# SCH_Control_unit.net
KiCad netlist of a schematic drawn in EasyEDA
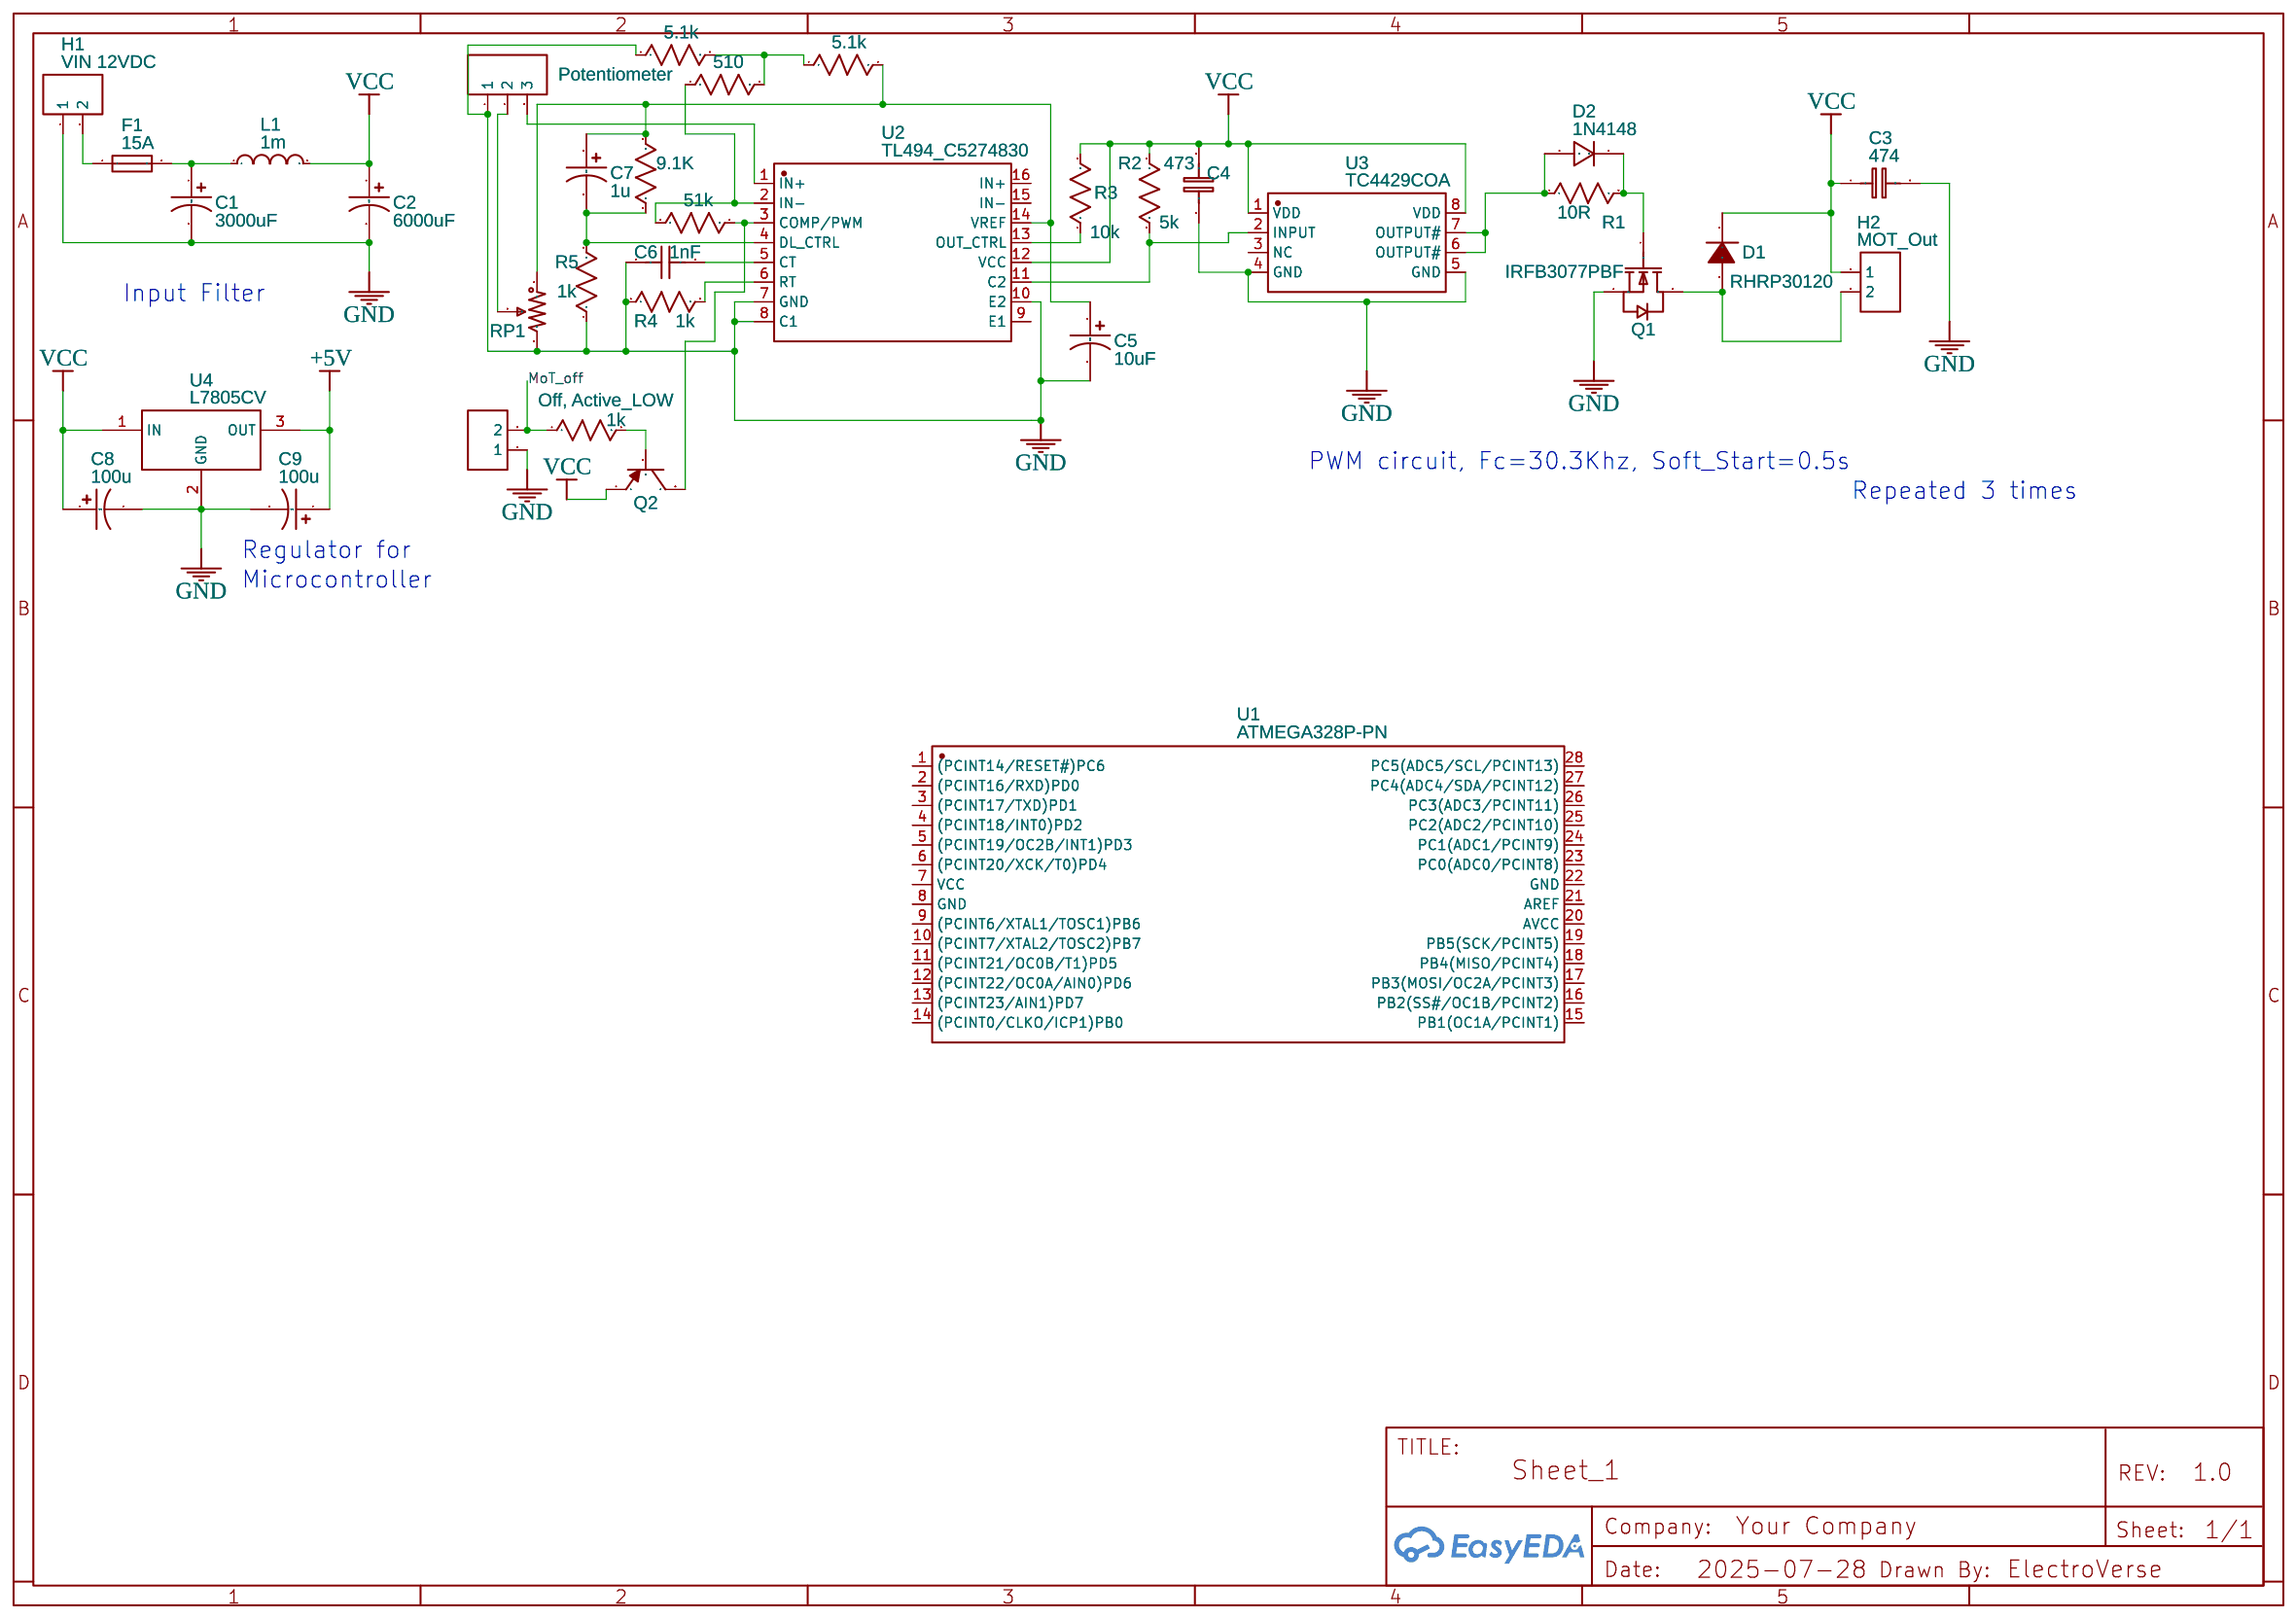
[diagram p0: schematic sheet]

(export (version "E")
  (design (tool "Eeschema 10.0.6"))
  (components
    (comp (ref "C1") (value "3000uF") (libsource (lib "") (part "C_Tan_SMD_A_US")))
    (comp (ref "C2") (value "6000uF") (libsource (lib "") (part "C_Tan_SMD_A_US")))
    (comp (ref "C3") (value "474") (libsource (lib "") (part "C_0603_EU")))
    (comp (ref "C4") (value "473") (libsource (lib "") (part "C_0603_EU_1")))
    (comp (ref "C5") (value "10uF") (libsource (lib "") (part "C_Tan_SMD_A_US_1")))
    (comp (ref "C6") (value "1nF") (libsource (lib "") (part "C_0603_US")))
    (comp (ref "C7") (value "1u") (libsource (lib "") (part "C_Tan_SMD_A_US_1")))
    (comp (ref "C8") (value "100u") (libsource (lib "") (part "C_Tan_SMD_A_US_2")))
    (comp (ref "C9") (value "100u") (libsource (lib "") (part "C_Tan_SMD_A_US_3")))
    (comp (ref "D1")
      (value "RHRP30120")
      (fields (field (name "Manufacturer") "onsemi(安森美)"))
      (libsource (lib "") (part "RHRP30120"))
    )
    (comp (ref "D2")
      (value "1N4148")
      (fields (field (name "Manufacturer") "FMS(美丽微)"))
      (libsource (lib "") (part "1N4148-C163750"))
    )
    (comp (ref "F1")
      (value "15A")
      (fields
        (field (name "Manufacturer Part") "37000500000")
        (field (name "Manufacturer") "Littelfuse(美国力特)")
      )
      (libsource (lib "") (part "37000500000"))
    )
    (comp (ref "H1") (value "VIN 12VDC") (libsource (lib "") (part "HDR-F-2.54_1x2_2")))
    (comp (ref "H2") (value "MOT_Out") (libsource (lib "") (part "HDR-F-2.54_1x2_1")))
    (comp (ref "H3") (value "Potentiometer") (libsource (lib "") (part "HDR-F-2.54_1x3")))
    (comp (ref "H4") (value "Off, Active_LOW") (libsource (lib "") (part "HDR-F-2.54_1x2")))
    (comp (ref "L1") (value "1m") (libsource (lib "") (part "L0603_US")))
    (comp (ref "Q1")
      (value "IRFB3077PBF")
      (fields (field (name "Manufacturer") "Infineon(英飞凌)"))
      (libsource (lib "") (part "IRFB3077PBF"))
    )
    (comp (ref "Q2")
      (value "2N3906(TO-92)")
      (fields (field (name "Manufacturer Part") "2N3906") (field (name "Manufacturer") "CJ"))
      (libsource (lib "") (part "2N3906(TO-92)"))
    )
    (comp (ref "R1") (value "10R") (libsource (lib "") (part "R_0603_US_1")))
    (comp (ref "R2") (value "5k") (libsource (lib "") (part "R_0603_US_2")))
    (comp (ref "R3") (value "10k") (libsource (lib "") (part "R_0603_US")))
    (comp (ref "R4") (value "1k") (libsource (lib "") (part "R_0603_US_1")))
    (comp (ref "R5") (value "1k") (libsource (lib "") (part "R_0603_US")))
    (comp (ref "R6") (value "9.1K") (libsource (lib "") (part "R_0603_US")))
    (comp (ref "R7") (value "51k") (libsource (lib "") (part "R_0603_US_1")))
    (comp (ref "R8") (value "5.1k") (libsource (lib "") (part "R_0603_US_1")))
    (comp (ref "R9") (value "5.1k") (libsource (lib "") (part "R_0603_US_1")))
    (comp (ref "R10") (value "510") (libsource (lib "") (part "R_0603_US_1")))
    (comp (ref "R11") (value "1k") (libsource (lib "") (part "R_0603_US_1")))
    (comp (ref "RP1") (value "R_3386P_US") (libsource (lib "") (part "R_3386P_US")))
    (comp (ref "U1")
      (value "ATMEGA328P-PN")
      (fields (field (name "Manufacturer") "MICROCHIP(美国微芯)"))
      (libsource (lib "") (part "ATMEGA328P-PN"))
    )
    (comp (ref "U2")
      (value "TL494_C5274830")
      (fields (field (name "Manufacturer Part") "TL494") (field (name "Manufacturer") "Sungine(双竞集成)"))
      (libsource (lib "") (part "TL494_C5274830"))
    )
    (comp (ref "U3")
      (value "TC4429COA")
      (fields (field (name "Manufacturer") "MICROCHIP(美国微芯)"))
      (libsource (lib "") (part "TC4429COA"))
    )
    (comp (ref "U4")
      (value "L7805CV")
      (fields (field (name "Manufacturer") "GOODWORK(固得沃克)"))
      (libsource (lib "") (part "L7805CV_C6430948"))
    )
  )
  (nets
    (net (code "1") (name "+5V") (class "Default")
      (node (ref "C9") (pin "1") (pinfunction "1_1") (pintype "unspecified"))
      (node (ref "U4") (pin "3") (pinfunction "OUT_3") (pintype "passive"))
    )
    (net (code "2") (name "/MoT_off") (class "Default")
      (node (ref "H4") (pin "2") (pinfunction "2_2") (pintype "input"))
      (node (ref "R11") (pin "1") (pinfunction "1_1") (pintype "unspecified"))
    )
    (net (code "3") (name "GND") (class "Default")
      (node (ref "C1") (pin "2") (pinfunction "2_2") (pintype "unspecified"))
      (node (ref "C2") (pin "2") (pinfunction "2_2") (pintype "unspecified"))
      (node (ref "C3") (pin "2") (pinfunction "2_2") (pintype "unspecified"))
      (node (ref "C4") (pin "1") (pinfunction "1_1") (pintype "unspecified"))
      (node (ref "C5") (pin "2") (pinfunction "2_2") (pintype "unspecified"))
      (node (ref "C6") (pin "1") (pinfunction "1_1") (pintype "unspecified"))
      (node (ref "C8") (pin "2") (pinfunction "2_2") (pintype "unspecified"))
      (node (ref "C9") (pin "2") (pinfunction "2_2") (pintype "unspecified"))
      (node (ref "H1") (pin "1") (pinfunction "1_1") (pintype "input"))
      (node (ref "H3") (pin "1") (pinfunction "1_1") (pintype "input"))
      (node (ref "H4") (pin "1") (pinfunction "1_1") (pintype "input"))
      (node (ref "Q1") (pin "3") (pinfunction "S_3") (pintype "unspecified"))
      (node (ref "R4") (pin "1") (pinfunction "1_1") (pintype "unspecified"))
      (node (ref "R5") (pin "1") (pinfunction "1_1") (pintype "unspecified"))
      (node (ref "R8") (pin "1") (pinfunction "1_1") (pintype "unspecified"))
      (node (ref "RP1") (pin "3") (pinfunction "3_3") (pintype "unspecified"))
      (node (ref "U2") (pin "10") (pinfunction "E2_10") (pintype "unspecified"))
      (node (ref "U2") (pin "7") (pinfunction "GND_7") (pintype "unspecified"))
      (node (ref "U2") (pin "8") (pinfunction "C1_8") (pintype "unspecified"))
      (node (ref "U3") (pin "4") (pinfunction "GND_4") (pintype "unspecified"))
      (node (ref "U3") (pin "5") (pinfunction "GND_5") (pintype "unspecified"))
      (node (ref "U4") (pin "2") (pinfunction "GND_2") (pintype "passive"))
    )
    (net (code "4") (name "Net-(C1-Pad1)") (class "Default")
      (node (ref "C1") (pin "1") (pinfunction "1_1") (pintype "unspecified"))
      (node (ref "F1") (pin "2") (pinfunction "2_2") (pintype "unspecified"))
      (node (ref "L1") (pin "1") (pinfunction "1_1") (pintype "unspecified"))
    )
    (net (code "5") (name "Net-(D1-C)") (class "Default")
      (node (ref "D1") (pin "2") (pinfunction "C_2") (pintype "unspecified"))
      (node (ref "H2") (pin "2") (pinfunction "2_2") (pintype "input"))
      (node (ref "Q1") (pin "2") (pinfunction "D_2") (pintype "unspecified"))
    )
    (net (code "6") (name "Net-(D2-Pad2)") (class "Default")
      (node (ref "D2") (pin "2") (pinfunction "2_2") (pintype "unspecified"))
      (node (ref "R1") (pin "1") (pinfunction "1_1") (pintype "unspecified"))
      (node (ref "U3") (pin "6") (pinfunction "OUTPUT#_6") (pintype "unspecified"))
      (node (ref "U3") (pin "7") (pinfunction "OUTPUT#_7") (pintype "unspecified"))
    )
    (net (code "7") (name "Net-(F1-Pad1)") (class "Default")
      (node (ref "F1") (pin "1") (pinfunction "1_1") (pintype "unspecified"))
      (node (ref "H1") (pin "2") (pinfunction "2_2") (pintype "input"))
    )
    (net (code "8") (name "Net-(H3-Pad2)") (class "Default")
      (node (ref "H3") (pin "2") (pinfunction "2_2") (pintype "input"))
      (node (ref "RP1") (pin "2") (pinfunction "2_2") (pintype "unspecified"))
    )
    (net (code "9") (name "Net-(H3-Pad3)") (class "Default")
      (node (ref "H3") (pin "3") (pinfunction "3_3") (pintype "input"))
      (node (ref "U2") (pin "1") (pinfunction "IN+_1") (pintype "unspecified"))
    )
    (net (code "10") (name "Net-(Q1-G)") (class "Default")
      (node (ref "D2") (pin "1") (pinfunction "1_1") (pintype "unspecified"))
      (node (ref "Q1") (pin "1") (pinfunction "G_1") (pintype "unspecified"))
      (node (ref "R1") (pin "2") (pinfunction "2_2") (pintype "unspecified"))
    )
    (net (code "11") (name "Net-(Q2-B)") (class "Default")
      (node (ref "Q2") (pin "2") (pinfunction "B_2") (pintype "input"))
      (node (ref "R11") (pin "2") (pinfunction "2_2") (pintype "unspecified"))
    )
    (net (code "12") (name "Net-(Q2-C)") (class "Default")
      (node (ref "Q2") (pin "3") (pinfunction "C_3") (pintype "input"))
      (node (ref "R7") (pin "2") (pinfunction "2_2") (pintype "unspecified"))
      (node (ref "U2") (pin "3") (pinfunction "COMP/PWM_3") (pintype "unspecified"))
    )
    (net (code "13") (name "Net-(R10-Pad1)") (class "Default")
      (node (ref "R10") (pin "1") (pinfunction "1_1") (pintype "unspecified"))
      (node (ref "R7") (pin "1") (pinfunction "1_1") (pintype "unspecified"))
      (node (ref "U2") (pin "2") (pinfunction "IN-_2") (pintype "unspecified"))
    )
    (net (code "14") (name "Net-(R10-Pad2)") (class "Default")
      (node (ref "R10") (pin "2") (pinfunction "2_2") (pintype "unspecified"))
      (node (ref "R8") (pin "2") (pinfunction "2_2") (pintype "unspecified"))
      (node (ref "R9") (pin "1") (pinfunction "1_1") (pintype "unspecified"))
    )
    (net (code "15") (name "Net-(U2-C2)") (class "Default")
      (node (ref "R2") (pin "2") (pinfunction "2_2") (pintype "unspecified"))
      (node (ref "U2") (pin "11") (pinfunction "C2_11") (pintype "unspecified"))
      (node (ref "U3") (pin "2") (pinfunction "INPUT_2") (pintype "unspecified"))
    )
    (net (code "16") (name "Net-(U2-CT)") (class "Default")
      (node (ref "C6") (pin "2") (pinfunction "2_2") (pintype "unspecified"))
      (node (ref "U2") (pin "5") (pinfunction "CT_5") (pintype "unspecified"))
    )
    (net (code "17") (name "Net-(U2-DL_CTRL)") (class "Default")
      (node (ref "C7") (pin "2") (pinfunction "2_2") (pintype "unspecified"))
      (node (ref "R5") (pin "2") (pinfunction "2_2") (pintype "unspecified"))
      (node (ref "R6") (pin "1") (pinfunction "1_1") (pintype "unspecified"))
      (node (ref "U2") (pin "4") (pinfunction "DL_CTRL_4") (pintype "unspecified"))
    )
    (net (code "18") (name "Net-(U2-OUT_CTRL)") (class "Default")
      (node (ref "R3") (pin "1") (pinfunction "1_1") (pintype "unspecified"))
      (node (ref "U2") (pin "13") (pinfunction "OUT_CTRL_13") (pintype "unspecified"))
    )
    (net (code "19") (name "Net-(U2-RT)") (class "Default")
      (node (ref "R4") (pin "2") (pinfunction "2_2") (pintype "unspecified"))
      (node (ref "U2") (pin "6") (pinfunction "RT_6") (pintype "unspecified"))
    )
    (net (code "20") (name "Net-(U2-VREF)") (class "Default")
      (node (ref "C5") (pin "1") (pinfunction "1_1") (pintype "unspecified"))
      (node (ref "C7") (pin "1") (pinfunction "1_1") (pintype "unspecified"))
      (node (ref "R6") (pin "2") (pinfunction "2_2") (pintype "unspecified"))
      (node (ref "R9") (pin "2") (pinfunction "2_2") (pintype "unspecified"))
      (node (ref "RP1") (pin "1") (pinfunction "1_1") (pintype "unspecified"))
      (node (ref "U2") (pin "14") (pinfunction "VREF_14") (pintype "unspecified"))
    )
    (net (code "21") (name "VCC") (class "Default")
      (node (ref "C2") (pin "1") (pinfunction "1_1") (pintype "unspecified"))
      (node (ref "C3") (pin "1") (pinfunction "1_1") (pintype "unspecified"))
      (node (ref "C4") (pin "2") (pinfunction "2_2") (pintype "unspecified"))
      (node (ref "C8") (pin "1") (pinfunction "1_1") (pintype "unspecified"))
      (node (ref "D1") (pin "1") (pinfunction "A_1") (pintype "unspecified"))
      (node (ref "H2") (pin "1") (pinfunction "1_1") (pintype "input"))
      (node (ref "L1") (pin "2") (pinfunction "2_2") (pintype "unspecified"))
      (node (ref "Q2") (pin "1") (pinfunction "E_1") (pintype "input"))
      (node (ref "R2") (pin "1") (pinfunction "1_1") (pintype "unspecified"))
      (node (ref "R3") (pin "2") (pinfunction "2_2") (pintype "unspecified"))
      (node (ref "U2") (pin "12") (pinfunction "VCC_12") (pintype "unspecified"))
      (node (ref "U3") (pin "1") (pinfunction "VDD_1") (pintype "unspecified"))
      (node (ref "U3") (pin "8") (pinfunction "VDD_8") (pintype "unspecified"))
      (node (ref "U4") (pin "1") (pinfunction "IN_1") (pintype "passive"))
    )
    (net (code "22") (name "unconnected-(U1-(PCINT0{slash}CLKO{slash}ICP1)PB0-Pad14)") (class "Default")
      (node (ref "U1") (pin "14") (pinfunction "(PCINT0/CLKO/ICP1)PB0_14") (pintype "unspecified"))
    )
    (net (code "23") (name "unconnected-(U1-(PCINT6{slash}XTAL1{slash}TOSC1)PB6-Pad9)") (class "Default")
      (node (ref "U1") (pin "9") (pinfunction "(PCINT6/XTAL1/TOSC1)PB6_9") (pintype "unspecified"))
    )
    (net (code "24") (name "unconnected-(U1-(PCINT7{slash}XTAL2{slash}TOSC2)PB7-Pad10)") (class "Default")
      (node (ref "U1") (pin "10") (pinfunction "(PCINT7/XTAL2/TOSC2)PB7_10") (pintype "unspecified"))
    )
    (net (code "25") (name "unconnected-(U1-(PCINT14{slash}RESET#)PC6-Pad1)") (class "Default")
      (node (ref "U1") (pin "1") (pinfunction "(PCINT14/RESET#)PC6_1") (pintype "unspecified"))
    )
    (net (code "26") (name "unconnected-(U1-(PCINT16{slash}RXD)PD0-Pad2)") (class "Default")
      (node (ref "U1") (pin "2") (pinfunction "(PCINT16/RXD)PD0_2") (pintype "unspecified"))
    )
    (net (code "27") (name "unconnected-(U1-(PCINT17{slash}TXD)PD1-Pad3)") (class "Default")
      (node (ref "U1") (pin "3") (pinfunction "(PCINT17/TXD)PD1_3") (pintype "unspecified"))
    )
    (net (code "28") (name "unconnected-(U1-(PCINT18{slash}INT0)PD2-Pad4)") (class "Default")
      (node (ref "U1") (pin "4") (pinfunction "(PCINT18/INT0)PD2_4") (pintype "unspecified"))
    )
    (net (code "29") (name "unconnected-(U1-(PCINT19{slash}OC2B{slash}INT1)PD3-Pad5)") (class "Default")
      (node (ref "U1") (pin "5") (pinfunction "(PCINT19/OC2B/INT1)PD3_5") (pintype "unspecified"))
    )
    (net (code "30") (name "unconnected-(U1-(PCINT20{slash}XCK{slash}T0)PD4-Pad6)") (class "Default")
      (node (ref "U1") (pin "6") (pinfunction "(PCINT20/XCK/T0)PD4_6") (pintype "unspecified"))
    )
    (net (code "31") (name "unconnected-(U1-(PCINT21{slash}OC0B{slash}T1)PD5-Pad11)") (class "Default")
      (node (ref "U1") (pin "11") (pinfunction "(PCINT21/OC0B/T1)PD5_11") (pintype "unspecified"))
    )
    (net (code "32") (name "unconnected-(U1-(PCINT22{slash}OC0A{slash}AIN0)PD6-Pad12)") (class "Default")
      (node (ref "U1") (pin "12") (pinfunction "(PCINT22/OC0A/AIN0)PD6_12") (pintype "unspecified"))
    )
    (net (code "33") (name "unconnected-(U1-(PCINT23{slash}AIN1)PD7-Pad13)") (class "Default")
      (node (ref "U1") (pin "13") (pinfunction "(PCINT23/AIN1)PD7_13") (pintype "unspecified"))
    )
    (net (code "34") (name "unconnected-(U1-AREF-Pad21)") (class "Default")
      (node (ref "U1") (pin "21") (pinfunction "AREF_21") (pintype "unspecified"))
    )
    (net (code "35") (name "unconnected-(U1-AVCC-Pad20)") (class "Default")
      (node (ref "U1") (pin "20") (pinfunction "AVCC_20") (pintype "unspecified"))
    )
    (net (code "36") (name "unconnected-(U1-GND-Pad8)") (class "Default")
      (node (ref "U1") (pin "8") (pinfunction "GND_8") (pintype "unspecified"))
    )
    (net (code "37") (name "unconnected-(U1-GND-Pad22)") (class "Default")
      (node (ref "U1") (pin "22") (pinfunction "GND_22") (pintype "unspecified"))
    )
    (net (code "38") (name "unconnected-(U1-PB1(OC1A{slash}PCINT1)-Pad15)") (class "Default")
      (node (ref "U1") (pin "15") (pinfunction "PB1(OC1A/PCINT1)_15") (pintype "unspecified"))
    )
    (net (code "39") (name "unconnected-(U1-PB2(SS#{slash}OC1B{slash}PCINT2)-Pad16)") (class "Default")
      (node (ref "U1") (pin "16") (pinfunction "PB2(SS#/OC1B/PCINT2)_16") (pintype "unspecified"))
    )
    (net (code "40") (name "unconnected-(U1-PB3(MOSI{slash}OC2A{slash}PCINT3)-Pad17)") (class "Default")
      (node (ref "U1") (pin "17") (pinfunction "PB3(MOSI/OC2A/PCINT3)_17") (pintype "unspecified"))
    )
    (net (code "41") (name "unconnected-(U1-PB4(MISO{slash}PCINT4)-Pad18)") (class "Default")
      (node (ref "U1") (pin "18") (pinfunction "PB4(MISO/PCINT4)_18") (pintype "unspecified"))
    )
    (net (code "42") (name "unconnected-(U1-PB5(SCK{slash}PCINT5)-Pad19)") (class "Default")
      (node (ref "U1") (pin "19") (pinfunction "PB5(SCK/PCINT5)_19") (pintype "unspecified"))
    )
    (net (code "43") (name "unconnected-(U1-PC0(ADC0{slash}PCINT8)-Pad23)") (class "Default")
      (node (ref "U1") (pin "23") (pinfunction "PC0(ADC0/PCINT8)_23") (pintype "unspecified"))
    )
    (net (code "44") (name "unconnected-(U1-PC1(ADC1{slash}PCINT9)-Pad24)") (class "Default")
      (node (ref "U1") (pin "24") (pinfunction "PC1(ADC1/PCINT9)_24") (pintype "unspecified"))
    )
    (net (code "45") (name "unconnected-(U1-PC2(ADC2{slash}PCINT10)-Pad25)") (class "Default")
      (node (ref "U1") (pin "25") (pinfunction "PC2(ADC2/PCINT10)_25") (pintype "unspecified"))
    )
    (net (code "46") (name "unconnected-(U1-PC3(ADC3{slash}PCINT11)-Pad26)") (class "Default")
      (node (ref "U1") (pin "26") (pinfunction "PC3(ADC3/PCINT11)_26") (pintype "unspecified"))
    )
    (net (code "47") (name "unconnected-(U1-PC4(ADC4{slash}SDA{slash}PCINT12)-Pad27)") (class "Default")
      (node (ref "U1") (pin "27") (pinfunction "PC4(ADC4/SDA/PCINT12)_27") (pintype "unspecified"))
    )
    (net (code "48") (name "unconnected-(U1-PC5(ADC5{slash}SCL{slash}PCINT13)-Pad28)") (class "Default")
      (node (ref "U1") (pin "28") (pinfunction "PC5(ADC5/SCL/PCINT13)_28") (pintype "unspecified"))
    )
    (net (code "49") (name "unconnected-(U1-VCC-Pad7)") (class "Default")
      (node (ref "U1") (pin "7") (pinfunction "VCC_7") (pintype "unspecified"))
    )
    (net (code "50") (name "unconnected-(U2-E1-Pad9)") (class "Default")
      (node (ref "U2") (pin "9") (pinfunction "E1_9") (pintype "unspecified"))
    )
    (net (code "51") (name "unconnected-(U2-IN+-Pad16)") (class "Default")
      (node (ref "U2") (pin "16") (pinfunction "IN+_16") (pintype "unspecified"))
    )
    (net (code "52") (name "unconnected-(U2-IN--Pad15)") (class "Default")
      (node (ref "U2") (pin "15") (pinfunction "IN-_15") (pintype "unspecified"))
    )
    (net (code "53") (name "unconnected-(U3-NC-Pad3)") (class "Default")
      (node (ref "U3") (pin "3") (pinfunction "NC_3") (pintype "unspecified"))
    )
  )
)
